# msgeq7-bargraph1.net
KiCad netlist of a schematic drawn in EAGLE
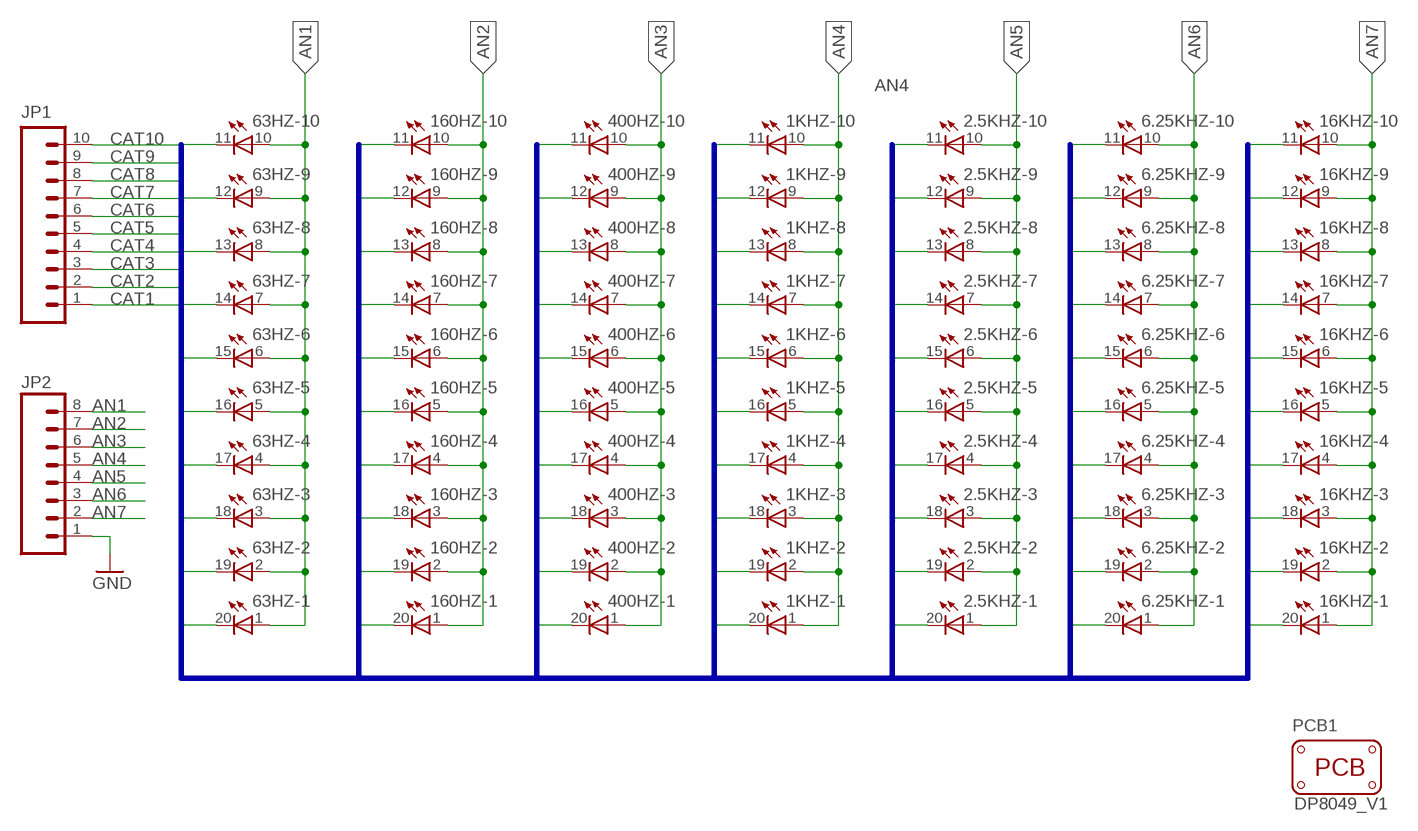
[diagram p0: schematic, sheet 1]

(export (version "E")
  (design (tool "Eeschema 10.0.6"))
  (components
    (comp (ref "1KHZ")
      (value "LB10")
      (footprint "eagle-import:LB10")
      (libsource (lib "eagle-import") (part "LB10"))
    )
    (comp (ref "2.5KHZ")
      (value "LB10")
      (footprint "eagle-import:LB10")
      (libsource (lib "eagle-import") (part "LB10"))
    )
    (comp (ref "6.25KHZ")
      (value "LB10")
      (footprint "eagle-import:LB10")
      (libsource (lib "eagle-import") (part "LB10"))
    )
    (comp (ref "16KHZ")
      (value "LB10")
      (footprint "eagle-import:LB10")
      (libsource (lib "eagle-import") (part "LB10"))
    )
    (comp (ref "63HZ")
      (value "LB10")
      (footprint "eagle-import:LB10")
      (libsource (lib "eagle-import") (part "LB10"))
    )
    (comp (ref "160HZ")
      (value "LB10")
      (footprint "eagle-import:LB10")
      (libsource (lib "eagle-import") (part "LB10"))
    )
    (comp (ref "400HZ")
      (value "LB10")
      (footprint "eagle-import:LB10")
      (libsource (lib "eagle-import") (part "LB10"))
    )
    (comp (ref "JP1")
      (value "M10\"")
      (footprint "eagle-import:1X10")
      (libsource (lib "eagle-import") (part "M10{dblquote}"))
    )
    (comp (ref "JP2")
      (value "M081X08")
      (footprint "eagle-import:1X08")
      (libsource (lib "eagle-import") (part "M081X08"))
    )
    (comp (ref "PCB1")
      (value "PCB_DP_RECTANGLE-80X49")
      (footprint "eagle-import:DP8049_V1")
      (libsource (lib "eagle-import") (part "PCB_DP_RECTANGLE-80X49"))
    )
  )
  (nets
    (net (code "1") (name "/CAT1") (class "Default")
      (node (ref "160HZ") (pin "20") (pinfunction "C_20") (pintype "passive"))
      (node (ref "16KHZ") (pin "20") (pinfunction "C_20") (pintype "passive"))
      (node (ref "1KHZ") (pin "20") (pinfunction "C_20") (pintype "passive"))
      (node (ref "2.5KHZ") (pin "20") (pinfunction "C_20") (pintype "passive"))
      (node (ref "400HZ") (pin "20") (pinfunction "C_20") (pintype "passive"))
      (node (ref "6.25KHZ") (pin "20") (pinfunction "C_20") (pintype "passive"))
      (node (ref "63HZ") (pin "20") (pinfunction "C_20") (pintype "passive"))
      (node (ref "JP1") (pin "1") (pinfunction "1_1") (pintype "passive"))
    )
    (net (code "2") (name "/CAT2") (class "Default")
      (node (ref "160HZ") (pin "19") (pinfunction "C_19") (pintype "passive"))
      (node (ref "16KHZ") (pin "19") (pinfunction "C_19") (pintype "passive"))
      (node (ref "1KHZ") (pin "19") (pinfunction "C_19") (pintype "passive"))
      (node (ref "2.5KHZ") (pin "19") (pinfunction "C_19") (pintype "passive"))
      (node (ref "400HZ") (pin "19") (pinfunction "C_19") (pintype "passive"))
      (node (ref "6.25KHZ") (pin "19") (pinfunction "C_19") (pintype "passive"))
      (node (ref "63HZ") (pin "19") (pinfunction "C_19") (pintype "passive"))
      (node (ref "JP1") (pin "2") (pinfunction "2_2") (pintype "passive"))
    )
    (net (code "3") (name "/CAT3") (class "Default")
      (node (ref "160HZ") (pin "18") (pinfunction "C_18") (pintype "passive"))
      (node (ref "16KHZ") (pin "18") (pinfunction "C_18") (pintype "passive"))
      (node (ref "1KHZ") (pin "18") (pinfunction "C_18") (pintype "passive"))
      (node (ref "2.5KHZ") (pin "18") (pinfunction "C_18") (pintype "passive"))
      (node (ref "400HZ") (pin "18") (pinfunction "C_18") (pintype "passive"))
      (node (ref "6.25KHZ") (pin "18") (pinfunction "C_18") (pintype "passive"))
      (node (ref "63HZ") (pin "18") (pinfunction "C_18") (pintype "passive"))
      (node (ref "JP1") (pin "3") (pinfunction "3_3") (pintype "passive"))
    )
    (net (code "4") (name "/CAT4") (class "Default")
      (node (ref "160HZ") (pin "17") (pinfunction "C_17") (pintype "passive"))
      (node (ref "16KHZ") (pin "17") (pinfunction "C_17") (pintype "passive"))
      (node (ref "1KHZ") (pin "17") (pinfunction "C_17") (pintype "passive"))
      (node (ref "2.5KHZ") (pin "17") (pinfunction "C_17") (pintype "passive"))
      (node (ref "400HZ") (pin "17") (pinfunction "C_17") (pintype "passive"))
      (node (ref "6.25KHZ") (pin "17") (pinfunction "C_17") (pintype "passive"))
      (node (ref "63HZ") (pin "17") (pinfunction "C_17") (pintype "passive"))
      (node (ref "JP1") (pin "4") (pinfunction "4_4") (pintype "passive"))
    )
    (net (code "5") (name "/CAT5") (class "Default")
      (node (ref "160HZ") (pin "16") (pinfunction "C_16") (pintype "passive"))
      (node (ref "16KHZ") (pin "16") (pinfunction "C_16") (pintype "passive"))
      (node (ref "1KHZ") (pin "16") (pinfunction "C_16") (pintype "passive"))
      (node (ref "2.5KHZ") (pin "16") (pinfunction "C_16") (pintype "passive"))
      (node (ref "400HZ") (pin "16") (pinfunction "C_16") (pintype "passive"))
      (node (ref "6.25KHZ") (pin "16") (pinfunction "C_16") (pintype "passive"))
      (node (ref "63HZ") (pin "16") (pinfunction "C_16") (pintype "passive"))
      (node (ref "JP1") (pin "5") (pinfunction "5_5") (pintype "passive"))
    )
    (net (code "6") (name "/CAT6") (class "Default")
      (node (ref "160HZ") (pin "15") (pinfunction "C_15") (pintype "passive"))
      (node (ref "16KHZ") (pin "15") (pinfunction "C_15") (pintype "passive"))
      (node (ref "1KHZ") (pin "15") (pinfunction "C_15") (pintype "passive"))
      (node (ref "2.5KHZ") (pin "15") (pinfunction "C_15") (pintype "passive"))
      (node (ref "400HZ") (pin "15") (pinfunction "C_15") (pintype "passive"))
      (node (ref "6.25KHZ") (pin "15") (pinfunction "C_15") (pintype "passive"))
      (node (ref "63HZ") (pin "15") (pinfunction "C_15") (pintype "passive"))
      (node (ref "JP1") (pin "6") (pinfunction "6_6") (pintype "passive"))
    )
    (net (code "7") (name "/CAT7") (class "Default")
      (node (ref "160HZ") (pin "14") (pinfunction "C_14") (pintype "passive"))
      (node (ref "16KHZ") (pin "14") (pinfunction "C_14") (pintype "passive"))
      (node (ref "1KHZ") (pin "14") (pinfunction "C_14") (pintype "passive"))
      (node (ref "2.5KHZ") (pin "14") (pinfunction "C_14") (pintype "passive"))
      (node (ref "400HZ") (pin "14") (pinfunction "C_14") (pintype "passive"))
      (node (ref "6.25KHZ") (pin "14") (pinfunction "C_14") (pintype "passive"))
      (node (ref "63HZ") (pin "14") (pinfunction "C_14") (pintype "passive"))
      (node (ref "JP1") (pin "7") (pinfunction "7_7") (pintype "passive"))
    )
    (net (code "8") (name "/CAT8") (class "Default")
      (node (ref "160HZ") (pin "13") (pinfunction "C_13") (pintype "passive"))
      (node (ref "16KHZ") (pin "13") (pinfunction "C_13") (pintype "passive"))
      (node (ref "1KHZ") (pin "13") (pinfunction "C_13") (pintype "passive"))
      (node (ref "2.5KHZ") (pin "13") (pinfunction "C_13") (pintype "passive"))
      (node (ref "400HZ") (pin "13") (pinfunction "C_13") (pintype "passive"))
      (node (ref "6.25KHZ") (pin "13") (pinfunction "C_13") (pintype "passive"))
      (node (ref "63HZ") (pin "13") (pinfunction "C_13") (pintype "passive"))
      (node (ref "JP1") (pin "8") (pinfunction "8_8") (pintype "passive"))
    )
    (net (code "9") (name "/CAT9") (class "Default")
      (node (ref "160HZ") (pin "12") (pinfunction "C_12") (pintype "passive"))
      (node (ref "16KHZ") (pin "12") (pinfunction "C_12") (pintype "passive"))
      (node (ref "1KHZ") (pin "12") (pinfunction "C_12") (pintype "passive"))
      (node (ref "2.5KHZ") (pin "12") (pinfunction "C_12") (pintype "passive"))
      (node (ref "400HZ") (pin "12") (pinfunction "C_12") (pintype "passive"))
      (node (ref "6.25KHZ") (pin "12") (pinfunction "C_12") (pintype "passive"))
      (node (ref "63HZ") (pin "12") (pinfunction "C_12") (pintype "passive"))
      (node (ref "JP1") (pin "9") (pinfunction "9_9") (pintype "passive"))
    )
    (net (code "10") (name "/CAT10") (class "Default")
      (node (ref "160HZ") (pin "11") (pinfunction "C_11") (pintype "passive"))
      (node (ref "16KHZ") (pin "11") (pinfunction "C_11") (pintype "passive"))
      (node (ref "1KHZ") (pin "11") (pinfunction "C_11") (pintype "passive"))
      (node (ref "2.5KHZ") (pin "11") (pinfunction "C_11") (pintype "passive"))
      (node (ref "400HZ") (pin "11") (pinfunction "C_11") (pintype "passive"))
      (node (ref "6.25KHZ") (pin "11") (pinfunction "C_11") (pintype "passive"))
      (node (ref "63HZ") (pin "11") (pinfunction "C_11") (pintype "passive"))
      (node (ref "JP1") (pin "10") (pinfunction "10_10") (pintype "passive"))
    )
    (net (code "11") (name "AN1") (class "Default")
      (node (ref "63HZ") (pin "1") (pinfunction "A_1") (pintype "passive"))
      (node (ref "63HZ") (pin "10") (pinfunction "A_10") (pintype "passive"))
      (node (ref "63HZ") (pin "2") (pinfunction "A_2") (pintype "passive"))
      (node (ref "63HZ") (pin "3") (pinfunction "A_3") (pintype "passive"))
      (node (ref "63HZ") (pin "4") (pinfunction "A_4") (pintype "passive"))
      (node (ref "63HZ") (pin "5") (pinfunction "A_5") (pintype "passive"))
      (node (ref "63HZ") (pin "6") (pinfunction "A_6") (pintype "passive"))
      (node (ref "63HZ") (pin "7") (pinfunction "A_7") (pintype "passive"))
      (node (ref "63HZ") (pin "8") (pinfunction "A_8") (pintype "passive"))
      (node (ref "63HZ") (pin "9") (pinfunction "A_9") (pintype "passive"))
      (node (ref "JP2") (pin "8") (pinfunction "8_8") (pintype "passive"))
    )
    (net (code "12") (name "AN2") (class "Default")
      (node (ref "160HZ") (pin "1") (pinfunction "A_1") (pintype "passive"))
      (node (ref "160HZ") (pin "10") (pinfunction "A_10") (pintype "passive"))
      (node (ref "160HZ") (pin "2") (pinfunction "A_2") (pintype "passive"))
      (node (ref "160HZ") (pin "3") (pinfunction "A_3") (pintype "passive"))
      (node (ref "160HZ") (pin "4") (pinfunction "A_4") (pintype "passive"))
      (node (ref "160HZ") (pin "5") (pinfunction "A_5") (pintype "passive"))
      (node (ref "160HZ") (pin "6") (pinfunction "A_6") (pintype "passive"))
      (node (ref "160HZ") (pin "7") (pinfunction "A_7") (pintype "passive"))
      (node (ref "160HZ") (pin "8") (pinfunction "A_8") (pintype "passive"))
      (node (ref "160HZ") (pin "9") (pinfunction "A_9") (pintype "passive"))
      (node (ref "JP2") (pin "7") (pinfunction "7_7") (pintype "passive"))
    )
    (net (code "13") (name "AN3") (class "Default")
      (node (ref "400HZ") (pin "1") (pinfunction "A_1") (pintype "passive"))
      (node (ref "400HZ") (pin "10") (pinfunction "A_10") (pintype "passive"))
      (node (ref "400HZ") (pin "2") (pinfunction "A_2") (pintype "passive"))
      (node (ref "400HZ") (pin "3") (pinfunction "A_3") (pintype "passive"))
      (node (ref "400HZ") (pin "4") (pinfunction "A_4") (pintype "passive"))
      (node (ref "400HZ") (pin "5") (pinfunction "A_5") (pintype "passive"))
      (node (ref "400HZ") (pin "6") (pinfunction "A_6") (pintype "passive"))
      (node (ref "400HZ") (pin "7") (pinfunction "A_7") (pintype "passive"))
      (node (ref "400HZ") (pin "8") (pinfunction "A_8") (pintype "passive"))
      (node (ref "400HZ") (pin "9") (pinfunction "A_9") (pintype "passive"))
      (node (ref "JP2") (pin "6") (pinfunction "6_6") (pintype "passive"))
    )
    (net (code "14") (name "AN4") (class "Default")
      (node (ref "1KHZ") (pin "1") (pinfunction "A_1") (pintype "passive"))
      (node (ref "1KHZ") (pin "10") (pinfunction "A_10") (pintype "passive"))
      (node (ref "1KHZ") (pin "2") (pinfunction "A_2") (pintype "passive"))
      (node (ref "1KHZ") (pin "3") (pinfunction "A_3") (pintype "passive"))
      (node (ref "1KHZ") (pin "4") (pinfunction "A_4") (pintype "passive"))
      (node (ref "1KHZ") (pin "5") (pinfunction "A_5") (pintype "passive"))
      (node (ref "1KHZ") (pin "6") (pinfunction "A_6") (pintype "passive"))
      (node (ref "1KHZ") (pin "7") (pinfunction "A_7") (pintype "passive"))
      (node (ref "1KHZ") (pin "8") (pinfunction "A_8") (pintype "passive"))
      (node (ref "1KHZ") (pin "9") (pinfunction "A_9") (pintype "passive"))
      (node (ref "JP2") (pin "5") (pinfunction "5_5") (pintype "passive"))
    )
    (net (code "15") (name "AN5") (class "Default")
      (node (ref "2.5KHZ") (pin "1") (pinfunction "A_1") (pintype "passive"))
      (node (ref "2.5KHZ") (pin "10") (pinfunction "A_10") (pintype "passive"))
      (node (ref "2.5KHZ") (pin "2") (pinfunction "A_2") (pintype "passive"))
      (node (ref "2.5KHZ") (pin "3") (pinfunction "A_3") (pintype "passive"))
      (node (ref "2.5KHZ") (pin "4") (pinfunction "A_4") (pintype "passive"))
      (node (ref "2.5KHZ") (pin "5") (pinfunction "A_5") (pintype "passive"))
      (node (ref "2.5KHZ") (pin "6") (pinfunction "A_6") (pintype "passive"))
      (node (ref "2.5KHZ") (pin "7") (pinfunction "A_7") (pintype "passive"))
      (node (ref "2.5KHZ") (pin "8") (pinfunction "A_8") (pintype "passive"))
      (node (ref "2.5KHZ") (pin "9") (pinfunction "A_9") (pintype "passive"))
      (node (ref "JP2") (pin "4") (pinfunction "4_4") (pintype "passive"))
    )
    (net (code "16") (name "AN6") (class "Default")
      (node (ref "6.25KHZ") (pin "1") (pinfunction "A_1") (pintype "passive"))
      (node (ref "6.25KHZ") (pin "10") (pinfunction "A_10") (pintype "passive"))
      (node (ref "6.25KHZ") (pin "2") (pinfunction "A_2") (pintype "passive"))
      (node (ref "6.25KHZ") (pin "3") (pinfunction "A_3") (pintype "passive"))
      (node (ref "6.25KHZ") (pin "4") (pinfunction "A_4") (pintype "passive"))
      (node (ref "6.25KHZ") (pin "5") (pinfunction "A_5") (pintype "passive"))
      (node (ref "6.25KHZ") (pin "6") (pinfunction "A_6") (pintype "passive"))
      (node (ref "6.25KHZ") (pin "7") (pinfunction "A_7") (pintype "passive"))
      (node (ref "6.25KHZ") (pin "8") (pinfunction "A_8") (pintype "passive"))
      (node (ref "6.25KHZ") (pin "9") (pinfunction "A_9") (pintype "passive"))
      (node (ref "JP2") (pin "3") (pinfunction "3_3") (pintype "passive"))
    )
    (net (code "17") (name "AN7") (class "Default")
      (node (ref "16KHZ") (pin "1") (pinfunction "A_1") (pintype "passive"))
      (node (ref "16KHZ") (pin "10") (pinfunction "A_10") (pintype "passive"))
      (node (ref "16KHZ") (pin "2") (pinfunction "A_2") (pintype "passive"))
      (node (ref "16KHZ") (pin "3") (pinfunction "A_3") (pintype "passive"))
      (node (ref "16KHZ") (pin "4") (pinfunction "A_4") (pintype "passive"))
      (node (ref "16KHZ") (pin "5") (pinfunction "A_5") (pintype "passive"))
      (node (ref "16KHZ") (pin "6") (pinfunction "A_6") (pintype "passive"))
      (node (ref "16KHZ") (pin "7") (pinfunction "A_7") (pintype "passive"))
      (node (ref "16KHZ") (pin "8") (pinfunction "A_8") (pintype "passive"))
      (node (ref "16KHZ") (pin "9") (pinfunction "A_9") (pintype "passive"))
      (node (ref "JP2") (pin "2") (pinfunction "2_2") (pintype "passive"))
    )
    (net (code "18") (name "GND") (class "Default")
      (node (ref "JP2") (pin "1") (pinfunction "1_1") (pintype "passive"))
    )
  )
)
